# Cubesat_Potencia_Painel_Solar.net
KiCad netlist of a schematic drawn in EAGLE
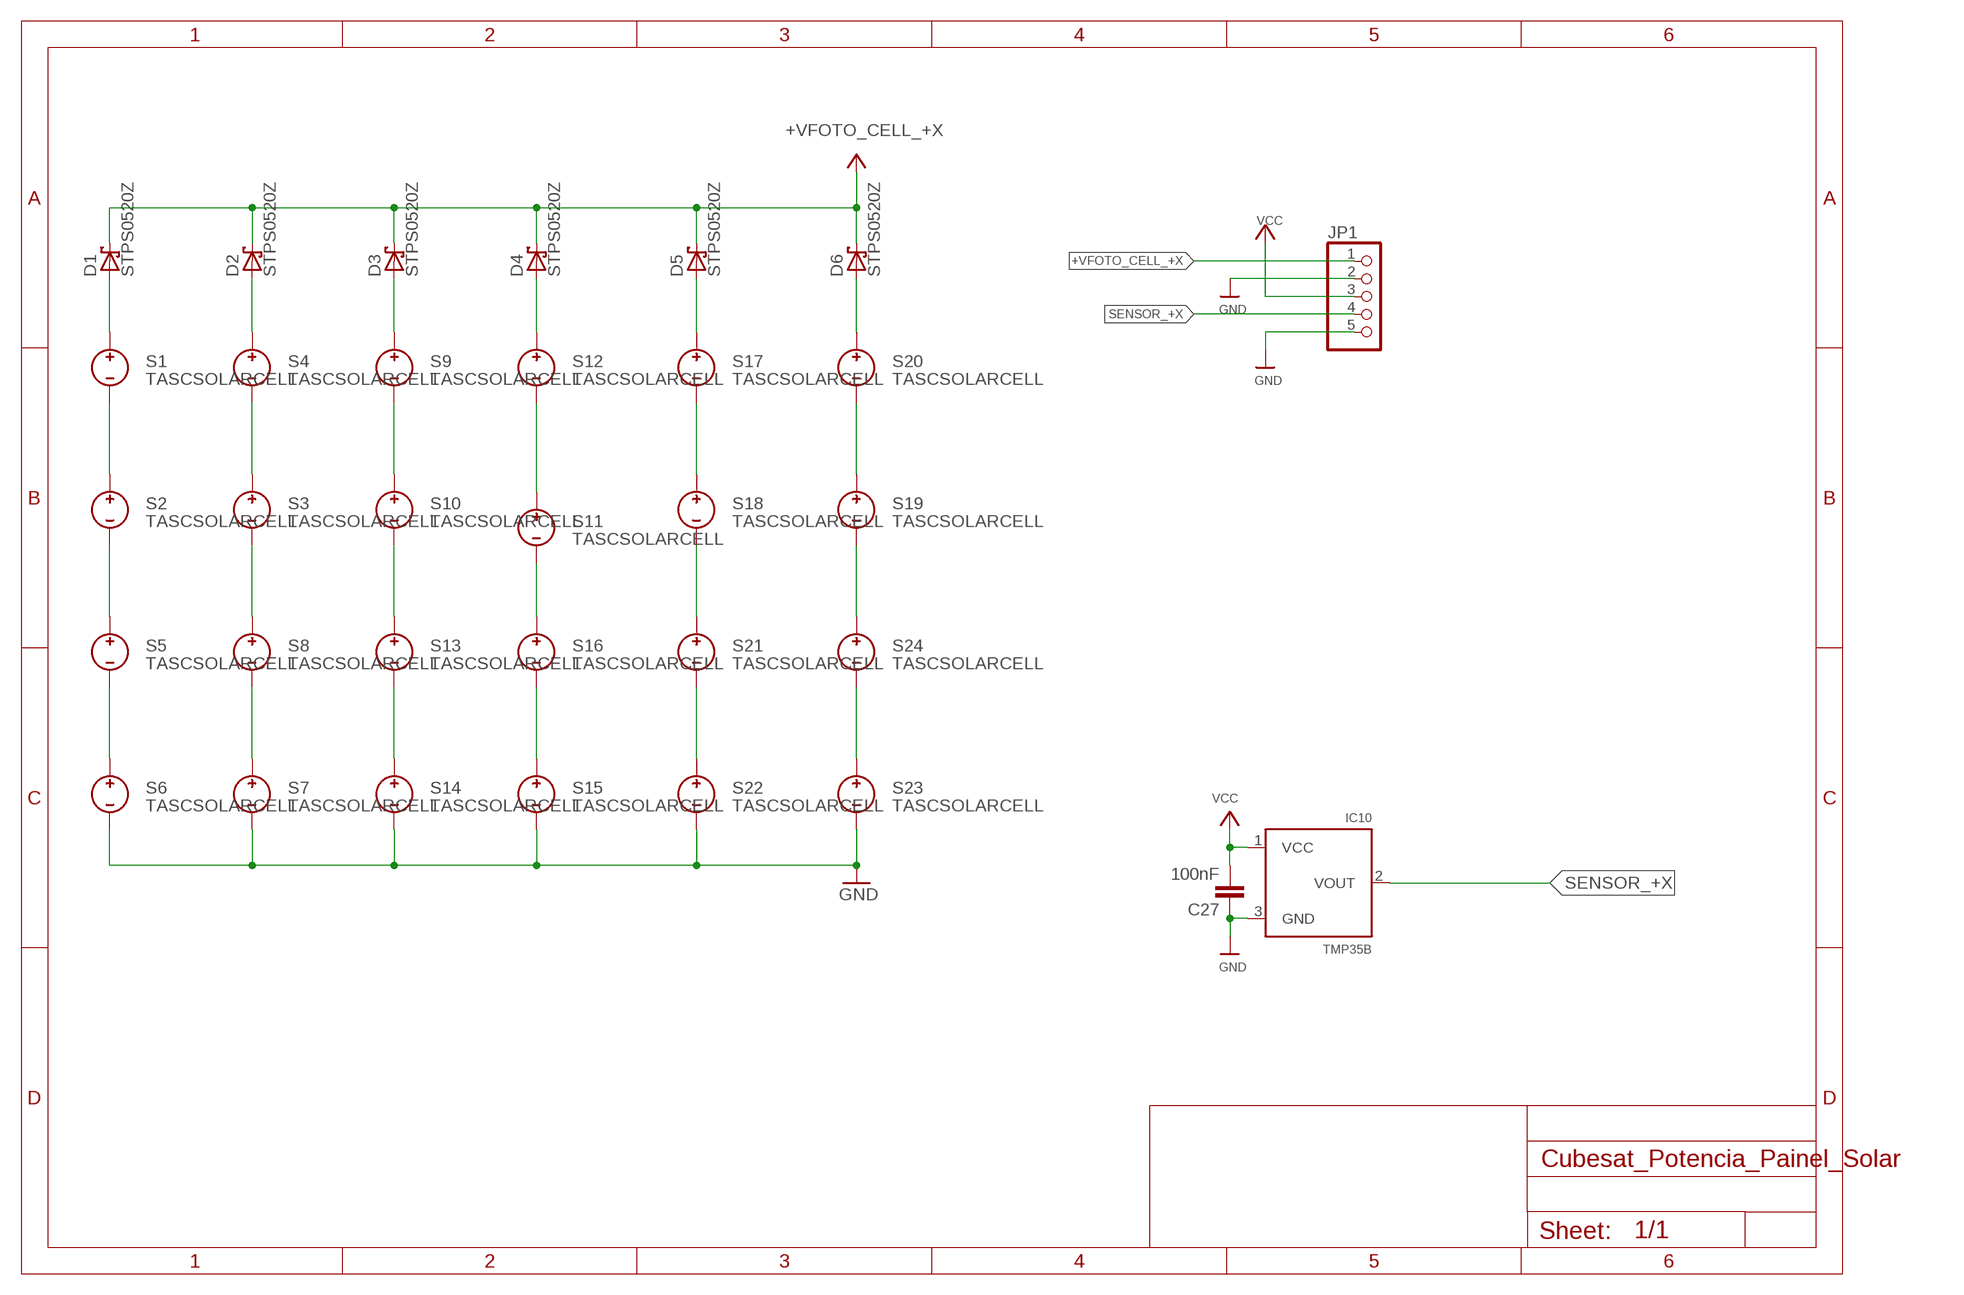
[diagram p0: schematic, sheet 1]

(export (version "E")
  (design (tool "Eeschema 10.0.6"))
  (components
    (comp (ref "C27")
      (value "100nF")
      (footprint "eagle-import:C0805")
      (libsource (lib "eagle-import") (part "C-EUC0805"))
    )
    (comp (ref "D1")
      (value "STPS0520Z")
      (footprint "eagle-import:SOD-123")
      (libsource (lib "eagle-import") (part "STPS0520Z"))
    )
    (comp (ref "D2")
      (value "STPS0520Z")
      (footprint "eagle-import:SOD-123")
      (libsource (lib "eagle-import") (part "STPS0520Z"))
    )
    (comp (ref "D3")
      (value "STPS0520Z")
      (footprint "eagle-import:SOD-123")
      (libsource (lib "eagle-import") (part "STPS0520Z"))
    )
    (comp (ref "D4")
      (value "STPS0520Z")
      (footprint "eagle-import:SOD-123")
      (libsource (lib "eagle-import") (part "STPS0520Z"))
    )
    (comp (ref "D5")
      (value "STPS0520Z")
      (footprint "eagle-import:SOD-123")
      (libsource (lib "eagle-import") (part "STPS0520Z"))
    )
    (comp (ref "D6")
      (value "STPS0520Z")
      (footprint "eagle-import:SOD-123")
      (libsource (lib "eagle-import") (part "STPS0520Z"))
    )
    (comp (ref "IC10")
      (value "TMP35B")
      (footprint "eagle-import:TO92-LINE")
      (libsource (lib "eagle-import") (part "TMP35B"))
    )
    (comp (ref "JP1")
      (value "HEADER-1X5SMT")
      (footprint "eagle-import:1X05_SMT")
      (libsource (lib "eagle-import") (part "HEADER-1X5SMT"))
    )
    (comp (ref "S1")
      (value "TASCSOLARCELL")
      (footprint "eagle-import:TASCSOLARCELL")
      (libsource (lib "eagle-import") (part "TASCSOLARCELL"))
    )
    (comp (ref "S2")
      (value "TASCSOLARCELL")
      (footprint "eagle-import:TASCSOLARCELL")
      (libsource (lib "eagle-import") (part "TASCSOLARCELL"))
    )
    (comp (ref "S3")
      (value "TASCSOLARCELL")
      (footprint "eagle-import:TASCSOLARCELL")
      (libsource (lib "eagle-import") (part "TASCSOLARCELL"))
    )
    (comp (ref "S4")
      (value "TASCSOLARCELL")
      (footprint "eagle-import:TASCSOLARCELL")
      (libsource (lib "eagle-import") (part "TASCSOLARCELL"))
    )
    (comp (ref "S5")
      (value "TASCSOLARCELL")
      (footprint "eagle-import:TASCSOLARCELL")
      (libsource (lib "eagle-import") (part "TASCSOLARCELL"))
    )
    (comp (ref "S6")
      (value "TASCSOLARCELL")
      (footprint "eagle-import:TASCSOLARCELL")
      (libsource (lib "eagle-import") (part "TASCSOLARCELL"))
    )
    (comp (ref "S7")
      (value "TASCSOLARCELL")
      (footprint "eagle-import:TASCSOLARCELL")
      (libsource (lib "eagle-import") (part "TASCSOLARCELL"))
    )
    (comp (ref "S8")
      (value "TASCSOLARCELL")
      (footprint "eagle-import:TASCSOLARCELL")
      (libsource (lib "eagle-import") (part "TASCSOLARCELL"))
    )
    (comp (ref "S9")
      (value "TASCSOLARCELL")
      (footprint "eagle-import:TASCSOLARCELL")
      (libsource (lib "eagle-import") (part "TASCSOLARCELL"))
    )
    (comp (ref "S10")
      (value "TASCSOLARCELL")
      (footprint "eagle-import:TASCSOLARCELL")
      (libsource (lib "eagle-import") (part "TASCSOLARCELL"))
    )
    (comp (ref "S11")
      (value "TASCSOLARCELL")
      (footprint "eagle-import:TASCSOLARCELL")
      (libsource (lib "eagle-import") (part "TASCSOLARCELL"))
    )
    (comp (ref "S12")
      (value "TASCSOLARCELL")
      (footprint "eagle-import:TASCSOLARCELL")
      (libsource (lib "eagle-import") (part "TASCSOLARCELL"))
    )
    (comp (ref "S13")
      (value "TASCSOLARCELL")
      (footprint "eagle-import:TASCSOLARCELL")
      (libsource (lib "eagle-import") (part "TASCSOLARCELL"))
    )
    (comp (ref "S14")
      (value "TASCSOLARCELL")
      (footprint "eagle-import:TASCSOLARCELL")
      (libsource (lib "eagle-import") (part "TASCSOLARCELL"))
    )
    (comp (ref "S15")
      (value "TASCSOLARCELL")
      (footprint "eagle-import:TASCSOLARCELL")
      (libsource (lib "eagle-import") (part "TASCSOLARCELL"))
    )
    (comp (ref "S16")
      (value "TASCSOLARCELL")
      (footprint "eagle-import:TASCSOLARCELL")
      (libsource (lib "eagle-import") (part "TASCSOLARCELL"))
    )
    (comp (ref "S17")
      (value "TASCSOLARCELL")
      (footprint "eagle-import:TASCSOLARCELL")
      (libsource (lib "eagle-import") (part "TASCSOLARCELL"))
    )
    (comp (ref "S18")
      (value "TASCSOLARCELL")
      (footprint "eagle-import:TASCSOLARCELL")
      (libsource (lib "eagle-import") (part "TASCSOLARCELL"))
    )
    (comp (ref "S19")
      (value "TASCSOLARCELL")
      (footprint "eagle-import:TASCSOLARCELL")
      (libsource (lib "eagle-import") (part "TASCSOLARCELL"))
    )
    (comp (ref "S20")
      (value "TASCSOLARCELL")
      (footprint "eagle-import:TASCSOLARCELL")
      (libsource (lib "eagle-import") (part "TASCSOLARCELL"))
    )
    (comp (ref "S21")
      (value "TASCSOLARCELL")
      (footprint "eagle-import:TASCSOLARCELL")
      (libsource (lib "eagle-import") (part "TASCSOLARCELL"))
    )
    (comp (ref "S22")
      (value "TASCSOLARCELL")
      (footprint "eagle-import:TASCSOLARCELL")
      (libsource (lib "eagle-import") (part "TASCSOLARCELL"))
    )
    (comp (ref "S23")
      (value "TASCSOLARCELL")
      (footprint "eagle-import:TASCSOLARCELL")
      (libsource (lib "eagle-import") (part "TASCSOLARCELL"))
    )
    (comp (ref "S24")
      (value "TASCSOLARCELL")
      (footprint "eagle-import:TASCSOLARCELL")
      (libsource (lib "eagle-import") (part "TASCSOLARCELL"))
    )
  )
  (nets
    (net (code "1") (name "+VFOTO_CELL_+X") (class "Default")
      (node (ref "D1") (pin "C") (pinfunction "C_C") (pintype "passive"))
      (node (ref "D2") (pin "C") (pinfunction "C_C") (pintype "passive"))
      (node (ref "D3") (pin "C") (pinfunction "C_C") (pintype "passive"))
      (node (ref "D4") (pin "C") (pinfunction "C_C") (pintype "passive"))
      (node (ref "D5") (pin "C") (pinfunction "C_C") (pintype "passive"))
      (node (ref "D6") (pin "C") (pinfunction "C_C") (pintype "passive"))
      (node (ref "JP1") (pin "1") (pinfunction "1_1") (pintype "passive"))
    )
    (net (code "2") (name "GND") (class "Default")
      (node (ref "C27") (pin "1") (pinfunction "1_1") (pintype "passive"))
      (node (ref "IC10") (pin "3") (pinfunction "GND_3") (pintype "bidirectional"))
      (node (ref "JP1") (pin "2") (pinfunction "2_2") (pintype "passive"))
      (node (ref "JP1") (pin "5") (pinfunction "5_5") (pintype "passive"))
      (node (ref "S14") (pin "N") (pinfunction "N_N") (pintype "power_in"))
      (node (ref "S15") (pin "N") (pinfunction "N_N") (pintype "power_in"))
      (node (ref "S22") (pin "N") (pinfunction "N_N") (pintype "power_in"))
      (node (ref "S23") (pin "N") (pinfunction "N_N") (pintype "power_in"))
      (node (ref "S6") (pin "N") (pinfunction "N_N") (pintype "power_in"))
      (node (ref "S7") (pin "N") (pinfunction "N_N") (pintype "power_in"))
    )
    (net (code "3") (name "Net-(D1-PadA)") (class "Default")
      (node (ref "D1") (pin "A") (pinfunction "A_A") (pintype "passive"))
      (node (ref "S1") (pin "P") (pinfunction "P_P") (pintype "power_in"))
    )
    (net (code "4") (name "Net-(D2-PadA)") (class "Default")
      (node (ref "D2") (pin "A") (pinfunction "A_A") (pintype "passive"))
      (node (ref "S4") (pin "P") (pinfunction "P_P") (pintype "power_in"))
    )
    (net (code "5") (name "Net-(D3-PadA)") (class "Default")
      (node (ref "D3") (pin "A") (pinfunction "A_A") (pintype "passive"))
      (node (ref "S9") (pin "P") (pinfunction "P_P") (pintype "power_in"))
    )
    (net (code "6") (name "Net-(D4-PadA)") (class "Default")
      (node (ref "D4") (pin "A") (pinfunction "A_A") (pintype "passive"))
      (node (ref "S12") (pin "P") (pinfunction "P_P") (pintype "power_in"))
    )
    (net (code "7") (name "Net-(D5-PadA)") (class "Default")
      (node (ref "D5") (pin "A") (pinfunction "A_A") (pintype "passive"))
      (node (ref "S17") (pin "P") (pinfunction "P_P") (pintype "power_in"))
    )
    (net (code "8") (name "Net-(D6-PadA)") (class "Default")
      (node (ref "D6") (pin "A") (pinfunction "A_A") (pintype "passive"))
      (node (ref "S20") (pin "P") (pinfunction "P_P") (pintype "power_in"))
    )
    (net (code "9") (name "Net-(S1-PadN)") (class "Default")
      (node (ref "S1") (pin "N") (pinfunction "N_N") (pintype "power_in"))
      (node (ref "S2") (pin "P") (pinfunction "P_P") (pintype "power_in"))
    )
    (net (code "10") (name "Net-(S2-PadN)") (class "Default")
      (node (ref "S2") (pin "N") (pinfunction "N_N") (pintype "power_in"))
      (node (ref "S5") (pin "P") (pinfunction "P_P") (pintype "power_in"))
    )
    (net (code "11") (name "Net-(S3-PadN)") (class "Default")
      (node (ref "S3") (pin "N") (pinfunction "N_N") (pintype "power_in"))
      (node (ref "S8") (pin "P") (pinfunction "P_P") (pintype "power_in"))
    )
    (net (code "12") (name "Net-(S3-PadP)") (class "Default")
      (node (ref "S3") (pin "P") (pinfunction "P_P") (pintype "power_in"))
      (node (ref "S4") (pin "N") (pinfunction "N_N") (pintype "power_in"))
    )
    (net (code "13") (name "Net-(S5-PadN)") (class "Default")
      (node (ref "S5") (pin "N") (pinfunction "N_N") (pintype "power_in"))
      (node (ref "S6") (pin "P") (pinfunction "P_P") (pintype "power_in"))
    )
    (net (code "14") (name "Net-(S7-PadP)") (class "Default")
      (node (ref "S7") (pin "P") (pinfunction "P_P") (pintype "power_in"))
      (node (ref "S8") (pin "N") (pinfunction "N_N") (pintype "power_in"))
    )
    (net (code "15") (name "Net-(S10-PadN)") (class "Default")
      (node (ref "S10") (pin "N") (pinfunction "N_N") (pintype "power_in"))
      (node (ref "S13") (pin "P") (pinfunction "P_P") (pintype "power_in"))
    )
    (net (code "16") (name "Net-(S10-PadP)") (class "Default")
      (node (ref "S10") (pin "P") (pinfunction "P_P") (pintype "power_in"))
      (node (ref "S9") (pin "N") (pinfunction "N_N") (pintype "power_in"))
    )
    (net (code "17") (name "Net-(S11-PadN)") (class "Default")
      (node (ref "S11") (pin "N") (pinfunction "N_N") (pintype "power_in"))
      (node (ref "S16") (pin "P") (pinfunction "P_P") (pintype "power_in"))
    )
    (net (code "18") (name "Net-(S11-PadP)") (class "Default")
      (node (ref "S11") (pin "P") (pinfunction "P_P") (pintype "power_in"))
      (node (ref "S12") (pin "N") (pinfunction "N_N") (pintype "power_in"))
    )
    (net (code "19") (name "Net-(S13-PadN)") (class "Default")
      (node (ref "S13") (pin "N") (pinfunction "N_N") (pintype "power_in"))
      (node (ref "S14") (pin "P") (pinfunction "P_P") (pintype "power_in"))
    )
    (net (code "20") (name "Net-(S15-PadP)") (class "Default")
      (node (ref "S15") (pin "P") (pinfunction "P_P") (pintype "power_in"))
      (node (ref "S16") (pin "N") (pinfunction "N_N") (pintype "power_in"))
    )
    (net (code "21") (name "Net-(S17-PadN)") (class "Default")
      (node (ref "S17") (pin "N") (pinfunction "N_N") (pintype "power_in"))
      (node (ref "S18") (pin "P") (pinfunction "P_P") (pintype "power_in"))
    )
    (net (code "22") (name "Net-(S18-PadN)") (class "Default")
      (node (ref "S18") (pin "N") (pinfunction "N_N") (pintype "power_in"))
      (node (ref "S21") (pin "P") (pinfunction "P_P") (pintype "power_in"))
    )
    (net (code "23") (name "Net-(S19-PadN)") (class "Default")
      (node (ref "S19") (pin "N") (pinfunction "N_N") (pintype "power_in"))
      (node (ref "S24") (pin "P") (pinfunction "P_P") (pintype "power_in"))
    )
    (net (code "24") (name "Net-(S19-PadP)") (class "Default")
      (node (ref "S19") (pin "P") (pinfunction "P_P") (pintype "power_in"))
      (node (ref "S20") (pin "N") (pinfunction "N_N") (pintype "power_in"))
    )
    (net (code "25") (name "Net-(S21-PadN)") (class "Default")
      (node (ref "S21") (pin "N") (pinfunction "N_N") (pintype "power_in"))
      (node (ref "S22") (pin "P") (pinfunction "P_P") (pintype "power_in"))
    )
    (net (code "26") (name "Net-(S23-PadP)") (class "Default")
      (node (ref "S23") (pin "P") (pinfunction "P_P") (pintype "power_in"))
      (node (ref "S24") (pin "N") (pinfunction "N_N") (pintype "power_in"))
    )
    (net (code "27") (name "SENSOR_+X") (class "Default")
      (node (ref "IC10") (pin "2") (pinfunction "VOUT_2") (pintype "bidirectional"))
      (node (ref "JP1") (pin "4") (pinfunction "4_4") (pintype "passive"))
    )
    (net (code "28") (name "VCC") (class "Default")
      (node (ref "C27") (pin "2") (pinfunction "2_2") (pintype "passive"))
      (node (ref "IC10") (pin "1") (pinfunction "VCC_1") (pintype "bidirectional"))
      (node (ref "JP1") (pin "3") (pinfunction "3_3") (pintype "passive"))
    )
  )
)
